# two_pieceboard_2.net
KiCad netlist of a schematic drawn in EAGLE
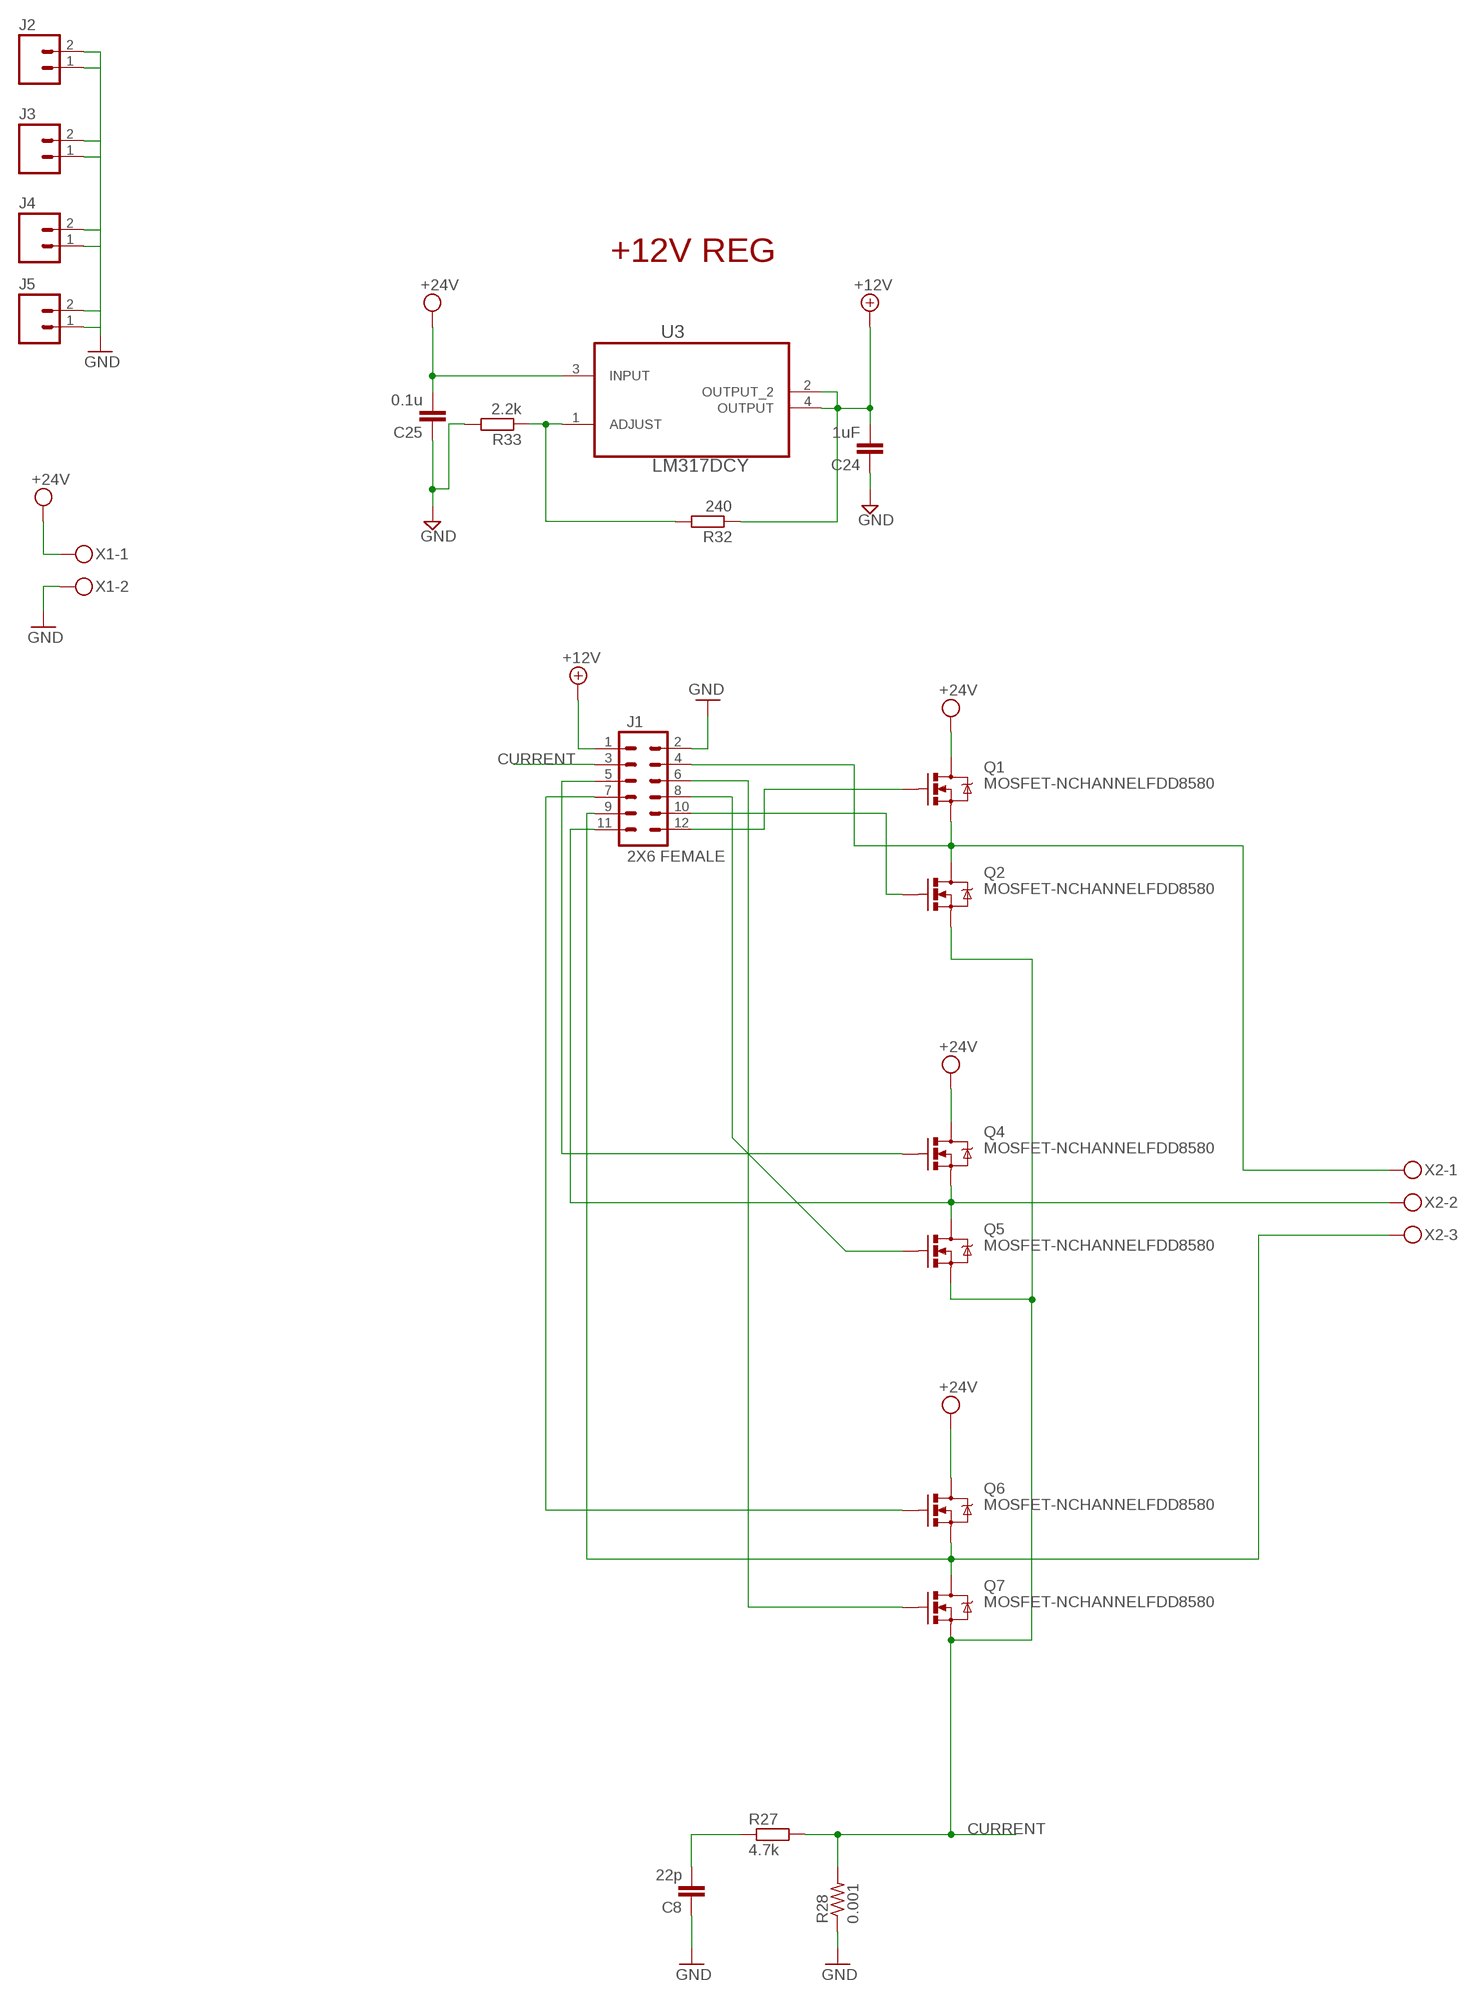
[diagram p0: schematic, sheet 1]

(export (version "E")
  (design (tool "Eeschema 10.0.6"))
  (components
    (comp (ref "C8")
      (value "22p")
      (footprint "eagle-import:C1206")
      (libsource (lib "eagle-import") (part "C-EUC1206"))
    )
    (comp (ref "C24")
      (value "1uF")
      (footprint "eagle-import:C1206")
      (libsource (lib "eagle-import") (part "C-EUC1206"))
    )
    (comp (ref "C25")
      (value "0.1u")
      (footprint "eagle-import:C1206")
      (libsource (lib "eagle-import") (part "C-EUC1206"))
    )
    (comp (ref "J1")
      (value "2X6 FEMALE")
      (footprint "eagle-import:2X6")
      (libsource (lib "eagle-import") (part "M06X2PTH_FEMALE"))
    )
    (comp (ref "J2")
      (value "M02PTH")
      (footprint "eagle-import:1X02")
      (libsource (lib "eagle-import") (part "M02PTH"))
    )
    (comp (ref "J3")
      (value "M02PTH")
      (footprint "eagle-import:1X02")
      (libsource (lib "eagle-import") (part "M02PTH"))
    )
    (comp (ref "J4")
      (value "M02PTH")
      (footprint "eagle-import:1X02")
      (libsource (lib "eagle-import") (part "M02PTH"))
    )
    (comp (ref "J5")
      (value "M02PTH")
      (footprint "eagle-import:1X02")
      (libsource (lib "eagle-import") (part "M02PTH"))
    )
    (comp (ref "Q1")
      (value "MOSFET-NCHANNELFDD8580")
      (footprint "eagle-import:DPAK")
      (libsource (lib "eagle-import") (part "MOSFET-NCHANNELFDD8580"))
    )
    (comp (ref "Q2")
      (value "MOSFET-NCHANNELFDD8580")
      (footprint "eagle-import:DPAK")
      (libsource (lib "eagle-import") (part "MOSFET-NCHANNELFDD8580"))
    )
    (comp (ref "Q4")
      (value "MOSFET-NCHANNELFDD8580")
      (footprint "eagle-import:DPAK")
      (libsource (lib "eagle-import") (part "MOSFET-NCHANNELFDD8580"))
    )
    (comp (ref "Q5")
      (value "MOSFET-NCHANNELFDD8580")
      (footprint "eagle-import:DPAK")
      (libsource (lib "eagle-import") (part "MOSFET-NCHANNELFDD8580"))
    )
    (comp (ref "Q6")
      (value "MOSFET-NCHANNELFDD8580")
      (footprint "eagle-import:DPAK")
      (libsource (lib "eagle-import") (part "MOSFET-NCHANNELFDD8580"))
    )
    (comp (ref "Q7")
      (value "MOSFET-NCHANNELFDD8580")
      (footprint "eagle-import:DPAK")
      (libsource (lib "eagle-import") (part "MOSFET-NCHANNELFDD8580"))
    )
    (comp (ref "R27")
      (value "4.7k")
      (footprint "eagle-import:R1206")
      (libsource (lib "eagle-import") (part "R-EU_R1206"))
    )
    (comp (ref "R28")
      (value "0.001")
      (footprint "eagle-import:R2512")
      (libsource (lib "eagle-import") (part "R-US_R2512"))
    )
    (comp (ref "R32")
      (value "240")
      (footprint "eagle-import:R1206")
      (libsource (lib "eagle-import") (part "R-EU_R1206"))
    )
    (comp (ref "R33")
      (value "2.2k")
      (footprint "eagle-import:R1206")
      (libsource (lib "eagle-import") (part "R-EU_R1206"))
    )
    (comp (ref "U3")
      (value "LM317DCY")
      (footprint "eagle-import:SOT230P700X180-4N")
      (libsource (lib "eagle-import") (part "LM317DCY"))
    )
    (comp (ref "X1")
      (value "MKDSN1,5/2-5,08")
      (footprint "eagle-import:MKDSN1,5_2-5,08")
      (fields (field (name "MPN") "MKDSN 1,5/2-5.08"))
      (libsource (lib "eagle-import") (part "MKDSN1,5/2-5,08"))
    )
    (comp (ref "X2")
      (value "MKDSN1,5/3-5,08")
      (footprint "eagle-import:MKDSN1,5_3-5,08")
      (fields (field (name "MPN") "SMKDSN1,5/3-5,08"))
      (libsource (lib "eagle-import") (part "MKDSN1,5/3-5,08"))
    )
  )
  (nets
    (net (code "1") (name "+12V") (class "Default")
      (node (ref "C24") (pin "2") (pinfunction "2_2") (pintype "passive"))
      (node (ref "J1") (pin "1") (pinfunction "1_1") (pintype "passive"))
      (node (ref "R32") (pin "1") (pinfunction "1_1") (pintype "passive"))
      (node (ref "U3") (pin "2") (pinfunction "OUTPUT_2_2") (pintype "output"))
      (node (ref "U3") (pin "4") (pinfunction "OUTPUT_4") (pintype "output"))
    )
    (net (code "2") (name "+24V") (class "Default")
      (node (ref "C25") (pin "2") (pinfunction "2_2") (pintype "passive"))
      (node (ref "Q1") (pin "4") (pinfunction "D_4") (pintype "passive"))
      (node (ref "Q4") (pin "4") (pinfunction "D_4") (pintype "passive"))
      (node (ref "Q6") (pin "4") (pinfunction "D_4") (pintype "passive"))
      (node (ref "U3") (pin "3") (pinfunction "INPUT_3") (pintype "input"))
      (node (ref "X1") (pin "1") (pinfunction "KL_1") (pintype "passive"))
    )
    (net (code "3") (name "/CURRENT") (class "Default")
      (node (ref "J1") (pin "3") (pinfunction "3_3") (pintype "passive"))
      (node (ref "Q2") (pin "3") (pinfunction "S_3") (pintype "passive"))
      (node (ref "Q5") (pin "3") (pinfunction "S_3") (pintype "passive"))
      (node (ref "Q7") (pin "3") (pinfunction "S_3") (pintype "passive"))
      (node (ref "R27") (pin "2") (pinfunction "2_2") (pintype "passive"))
      (node (ref "R28") (pin "2") (pinfunction "2_2") (pintype "passive"))
    )
    (net (code "4") (name "GND") (class "Default")
      (node (ref "C24") (pin "1") (pinfunction "1_1") (pintype "passive"))
      (node (ref "C25") (pin "1") (pinfunction "1_1") (pintype "passive"))
      (node (ref "C8") (pin "1") (pinfunction "1_1") (pintype "passive"))
      (node (ref "J1") (pin "2") (pinfunction "2_2") (pintype "passive"))
      (node (ref "J2") (pin "1") (pinfunction "1_1") (pintype "passive"))
      (node (ref "J2") (pin "2") (pinfunction "2_2") (pintype "passive"))
      (node (ref "J3") (pin "1") (pinfunction "1_1") (pintype "passive"))
      (node (ref "J3") (pin "2") (pinfunction "2_2") (pintype "passive"))
      (node (ref "J4") (pin "1") (pinfunction "1_1") (pintype "passive"))
      (node (ref "J4") (pin "2") (pinfunction "2_2") (pintype "passive"))
      (node (ref "J5") (pin "1") (pinfunction "1_1") (pintype "passive"))
      (node (ref "J5") (pin "2") (pinfunction "2_2") (pintype "passive"))
      (node (ref "R28") (pin "1") (pinfunction "1_1") (pintype "passive"))
      (node (ref "R33") (pin "2") (pinfunction "2_2") (pintype "passive"))
      (node (ref "X1") (pin "2") (pinfunction "KL_2") (pintype "passive"))
    )
    (net (code "5") (name "Net-(C8-Pad2)") (class "Default")
      (node (ref "C8") (pin "2") (pinfunction "2_2") (pintype "passive"))
      (node (ref "R27") (pin "1") (pinfunction "1_1") (pintype "passive"))
    )
    (net (code "6") (name "Net-(Q1-G)") (class "Default")
      (node (ref "J1") (pin "12") (pinfunction "12_12") (pintype "passive"))
      (node (ref "Q1") (pin "1") (pinfunction "G_1") (pintype "passive"))
    )
    (net (code "7") (name "Net-(Q1-S)") (class "Default")
      (node (ref "J1") (pin "4") (pinfunction "4_4") (pintype "passive"))
      (node (ref "Q1") (pin "3") (pinfunction "S_3") (pintype "passive"))
      (node (ref "Q2") (pin "4") (pinfunction "D_4") (pintype "passive"))
      (node (ref "X2") (pin "1") (pinfunction "KL_1") (pintype "passive"))
    )
    (net (code "8") (name "Net-(Q2-G)") (class "Default")
      (node (ref "J1") (pin "10") (pinfunction "10_10") (pintype "passive"))
      (node (ref "Q2") (pin "1") (pinfunction "G_1") (pintype "passive"))
    )
    (net (code "9") (name "Net-(Q4-G)") (class "Default")
      (node (ref "J1") (pin "5") (pinfunction "5_5") (pintype "passive"))
      (node (ref "Q4") (pin "1") (pinfunction "G_1") (pintype "passive"))
    )
    (net (code "10") (name "Net-(Q4-S)") (class "Default")
      (node (ref "J1") (pin "11") (pinfunction "11_11") (pintype "passive"))
      (node (ref "Q4") (pin "3") (pinfunction "S_3") (pintype "passive"))
      (node (ref "Q5") (pin "4") (pinfunction "D_4") (pintype "passive"))
      (node (ref "X2") (pin "2") (pinfunction "KL_2") (pintype "passive"))
    )
    (net (code "11") (name "Net-(Q5-G)") (class "Default")
      (node (ref "J1") (pin "8") (pinfunction "8_8") (pintype "passive"))
      (node (ref "Q5") (pin "1") (pinfunction "G_1") (pintype "passive"))
    )
    (net (code "12") (name "Net-(Q6-G)") (class "Default")
      (node (ref "J1") (pin "7") (pinfunction "7_7") (pintype "passive"))
      (node (ref "Q6") (pin "1") (pinfunction "G_1") (pintype "passive"))
    )
    (net (code "13") (name "Net-(Q6-S)") (class "Default")
      (node (ref "J1") (pin "9") (pinfunction "9_9") (pintype "passive"))
      (node (ref "Q6") (pin "3") (pinfunction "S_3") (pintype "passive"))
      (node (ref "Q7") (pin "4") (pinfunction "D_4") (pintype "passive"))
      (node (ref "X2") (pin "3") (pinfunction "KL_3") (pintype "passive"))
    )
    (net (code "14") (name "Net-(Q7-G)") (class "Default")
      (node (ref "J1") (pin "6") (pinfunction "6_6") (pintype "passive"))
      (node (ref "Q7") (pin "1") (pinfunction "G_1") (pintype "passive"))
    )
    (net (code "15") (name "Net-(U3-ADJUST)") (class "Default")
      (node (ref "R32") (pin "2") (pinfunction "2_2") (pintype "passive"))
      (node (ref "R33") (pin "1") (pinfunction "1_1") (pintype "passive"))
      (node (ref "U3") (pin "1") (pinfunction "ADJUST_1") (pintype "input"))
    )
  )
)
